# TTeC_Sheet1.net
KiCad netlist of a schematic drawn in Altium Designer
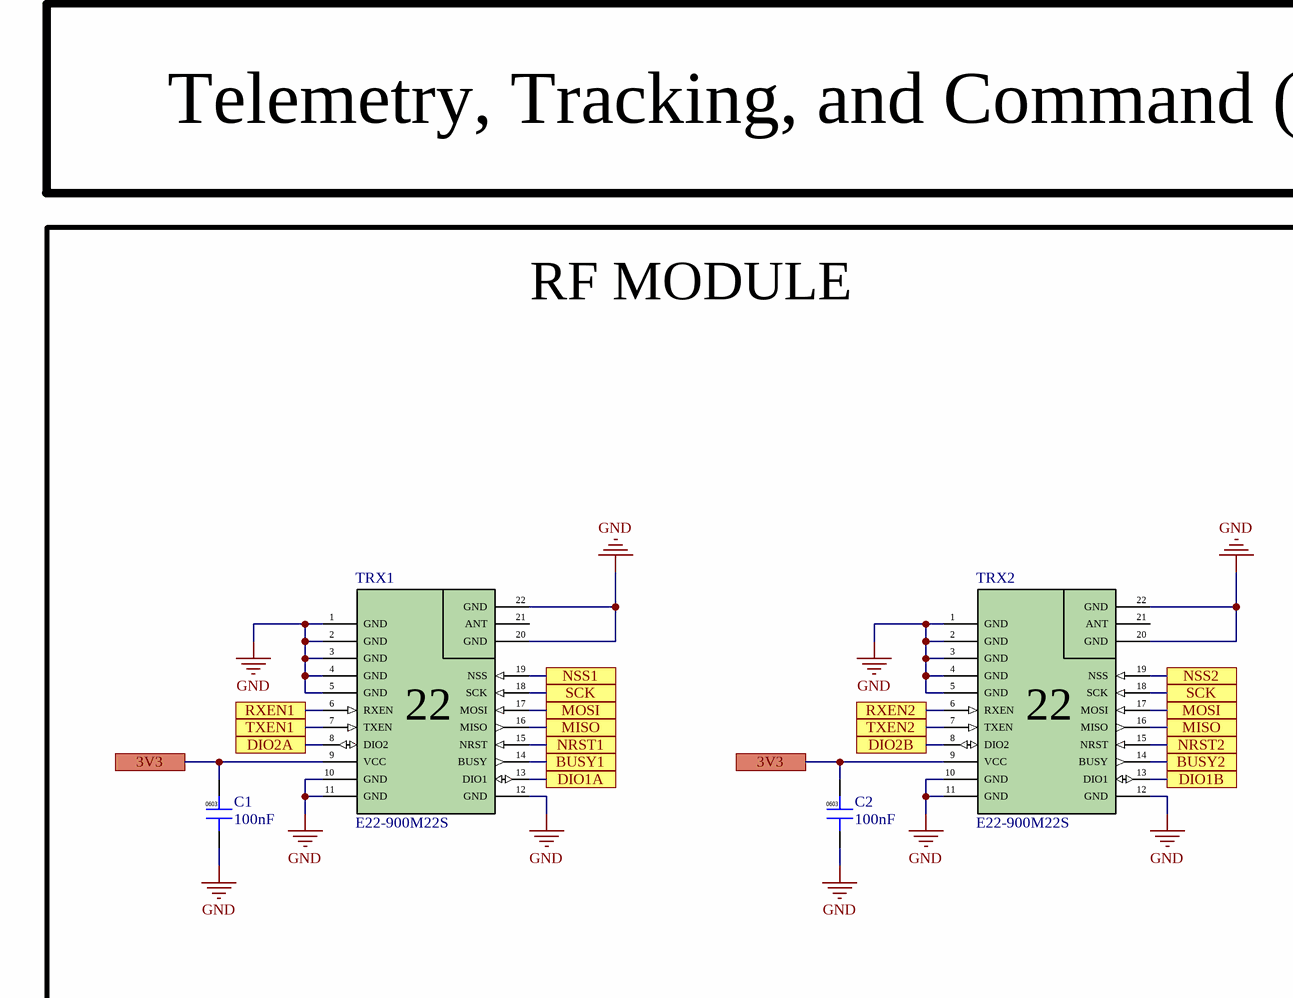
[diagram p0: TTeC_Sheet1.SchDoc, left]
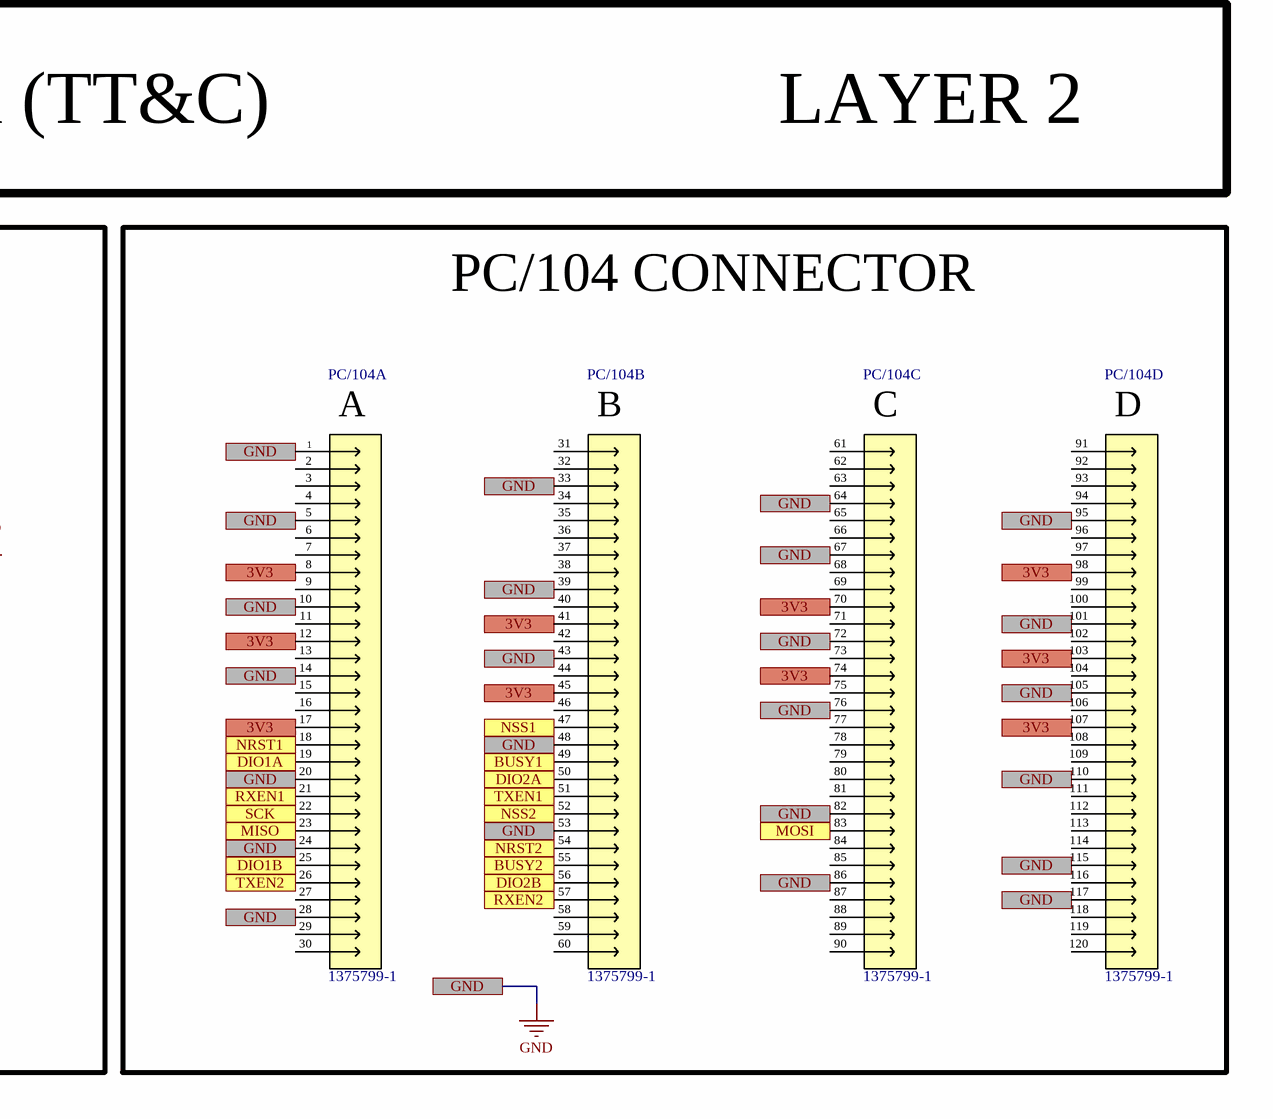
[diagram p1: TTeC_Sheet1.SchDoc, right]

(export (version "E")
  (design (tool "Eeschema 10.0.6"))
  (components
    (comp (ref "C1")
      (value "100nF")
      (footprint "CAP0603_060")
      (description "Capacitor SDM 0603")
      (libsource (lib "componentes_Henrique_V1") (part "CAP0603"))
    )
    (comp (ref "C2")
      (value "100nF")
      (footprint "CAP0603_060")
      (description "Capacitor SDM 0603")
      (libsource (lib "componentes_Henrique_V1") (part "CAP0603"))
    )
    (comp (ref "PC/104")
      (value "1375799-1")
      (footprint "1375799-1")
      (libsource (lib "componentes_Henrique_V1") (part "1375799-1"))
    )
    (comp (ref "TRX1")
      (value "E22-900M22S")
      (footprint "E22-900M22S")
      (libsource (lib "componentes_Henrique_V1") (part "E22-900M22S"))
    )
    (comp (ref "TRX2")
      (value "E22-900M22S")
      (footprint "E22-900M22S")
      (libsource (lib "componentes_Henrique_V1") (part "E22-900M22S"))
    )
  )
  (nets
    (net (code "1") (name "/3V3") (class "Default")
      (node (ref "C1") (pin "1") (pinfunction "1_1") (pintype "passive"))
      (node (ref "C2") (pin "1") (pinfunction "1_1") (pintype "passive"))
      (node (ref "PC/104") (pin "103") (pinfunction "103_103") (pintype "passive"))
      (node (ref "PC/104") (pin "107") (pinfunction "107_107") (pintype "passive"))
      (node (ref "PC/104") (pin "12") (pinfunction "12_12") (pintype "passive"))
      (node (ref "PC/104") (pin "17") (pinfunction "17_17") (pintype "passive"))
      (node (ref "PC/104") (pin "41") (pinfunction "41_41") (pintype "passive"))
      (node (ref "PC/104") (pin "45") (pinfunction "45_45") (pintype "passive"))
      (node (ref "PC/104") (pin "70") (pinfunction "70_70") (pintype "passive"))
      (node (ref "PC/104") (pin "74") (pinfunction "74_74") (pintype "passive"))
      (node (ref "PC/104") (pin "8") (pinfunction "8_8") (pintype "passive"))
      (node (ref "PC/104") (pin "98") (pinfunction "98_98") (pintype "passive"))
      (node (ref "TRX1") (pin "9") (pinfunction "VCC_9") (pintype "passive"))
      (node (ref "TRX2") (pin "9") (pinfunction "VCC_9") (pintype "passive"))
    )
    (net (code "2") (name "/BUSY1") (class "Default")
      (node (ref "PC/104") (pin "49") (pinfunction "49_49") (pintype "passive"))
      (node (ref "TRX1") (pin "14") (pinfunction "BUSY_14") (pintype "output"))
    )
    (net (code "3") (name "/BUSY2") (class "Default")
      (node (ref "PC/104") (pin "55") (pinfunction "55_55") (pintype "passive"))
      (node (ref "TRX2") (pin "14") (pinfunction "BUSY_14") (pintype "output"))
    )
    (net (code "4") (name "/DIO1A") (class "Default")
      (node (ref "PC/104") (pin "19") (pinfunction "19_19") (pintype "passive"))
      (node (ref "TRX1") (pin "13") (pinfunction "DIO1_13") (pintype "bidirectional"))
    )
    (net (code "5") (name "/DIO1B") (class "Default")
      (node (ref "PC/104") (pin "25") (pinfunction "25_25") (pintype "passive"))
      (node (ref "TRX2") (pin "13") (pinfunction "DIO1_13") (pintype "bidirectional"))
    )
    (net (code "6") (name "/DIO2A") (class "Default")
      (node (ref "PC/104") (pin "50") (pinfunction "50_50") (pintype "passive"))
      (node (ref "TRX1") (pin "8") (pinfunction "DIO2_8") (pintype "bidirectional"))
    )
    (net (code "7") (name "/DIO2B") (class "Default")
      (node (ref "PC/104") (pin "56") (pinfunction "56_56") (pintype "passive"))
      (node (ref "TRX2") (pin "8") (pinfunction "DIO2_8") (pintype "bidirectional"))
    )
    (net (code "8") (name "/MISO") (class "Default")
      (node (ref "PC/104") (pin "23") (pinfunction "23_23") (pintype "passive"))
      (node (ref "TRX1") (pin "16") (pinfunction "MISO_16") (pintype "output"))
      (node (ref "TRX2") (pin "16") (pinfunction "MISO_16") (pintype "output"))
    )
    (net (code "9") (name "/MOSI") (class "Default")
      (node (ref "PC/104") (pin "83") (pinfunction "83_83") (pintype "passive"))
      (node (ref "TRX1") (pin "17") (pinfunction "MOSI_17") (pintype "input"))
      (node (ref "TRX2") (pin "17") (pinfunction "MOSI_17") (pintype "input"))
    )
    (net (code "10") (name "/NRST1") (class "Default")
      (node (ref "PC/104") (pin "18") (pinfunction "18_18") (pintype "passive"))
      (node (ref "TRX1") (pin "15") (pinfunction "NRST_15") (pintype "input"))
    )
    (net (code "11") (name "/NRST2") (class "Default")
      (node (ref "PC/104") (pin "54") (pinfunction "54_54") (pintype "passive"))
      (node (ref "TRX2") (pin "15") (pinfunction "NRST_15") (pintype "input"))
    )
    (net (code "12") (name "/NSS1") (class "Default")
      (node (ref "PC/104") (pin "47") (pinfunction "47_47") (pintype "passive"))
      (node (ref "TRX1") (pin "19") (pinfunction "NSS_19") (pintype "input"))
    )
    (net (code "13") (name "/NSS2") (class "Default")
      (node (ref "PC/104") (pin "52") (pinfunction "52_52") (pintype "passive"))
      (node (ref "TRX2") (pin "19") (pinfunction "NSS_19") (pintype "input"))
    )
    (net (code "14") (name "/RXEN1") (class "Default")
      (node (ref "PC/104") (pin "21") (pinfunction "21_21") (pintype "passive"))
      (node (ref "TRX1") (pin "6") (pinfunction "RXEN_6") (pintype "input"))
    )
    (net (code "15") (name "/RXEN2") (class "Default")
      (node (ref "PC/104") (pin "57") (pinfunction "57_57") (pintype "passive"))
      (node (ref "TRX2") (pin "6") (pinfunction "RXEN_6") (pintype "input"))
    )
    (net (code "16") (name "/SCK") (class "Default")
      (node (ref "PC/104") (pin "22") (pinfunction "22_22") (pintype "passive"))
      (node (ref "TRX1") (pin "18") (pinfunction "SCK_18") (pintype "input"))
      (node (ref "TRX2") (pin "18") (pinfunction "SCK_18") (pintype "input"))
    )
    (net (code "17") (name "/TXEN1") (class "Default")
      (node (ref "PC/104") (pin "51") (pinfunction "51_51") (pintype "passive"))
      (node (ref "TRX1") (pin "7") (pinfunction "TXEN_7") (pintype "input"))
    )
    (net (code "18") (name "/TXEN2") (class "Default")
      (node (ref "PC/104") (pin "26") (pinfunction "26_26") (pintype "passive"))
      (node (ref "TRX2") (pin "7") (pinfunction "TXEN_7") (pintype "input"))
    )
    (net (code "19") (name "GND") (class "Default")
      (node (ref "C1") (pin "2") (pinfunction "2_2") (pintype "passive"))
      (node (ref "C2") (pin "2") (pinfunction "2_2") (pintype "passive"))
      (node (ref "PC/104") (pin "1") (pinfunction "1_1") (pintype "passive"))
      (node (ref "PC/104") (pin "10") (pinfunction "10_10") (pintype "passive"))
      (node (ref "PC/104") (pin "101") (pinfunction "101_101") (pintype "passive"))
      (node (ref "PC/104") (pin "105") (pinfunction "105_105") (pintype "passive"))
      (node (ref "PC/104") (pin "110") (pinfunction "110_110") (pintype "passive"))
      (node (ref "PC/104") (pin "115") (pinfunction "115_115") (pintype "passive"))
      (node (ref "PC/104") (pin "117") (pinfunction "117_117") (pintype "passive"))
      (node (ref "PC/104") (pin "14") (pinfunction "14_14") (pintype "passive"))
      (node (ref "PC/104") (pin "20") (pinfunction "20_20") (pintype "passive"))
      (node (ref "PC/104") (pin "24") (pinfunction "24_24") (pintype "passive"))
      (node (ref "PC/104") (pin "28") (pinfunction "28_28") (pintype "passive"))
      (node (ref "PC/104") (pin "33") (pinfunction "33_33") (pintype "passive"))
      (node (ref "PC/104") (pin "39") (pinfunction "39_39") (pintype "passive"))
      (node (ref "PC/104") (pin "43") (pinfunction "43_43") (pintype "passive"))
      (node (ref "PC/104") (pin "48") (pinfunction "48_48") (pintype "passive"))
      (node (ref "PC/104") (pin "5") (pinfunction "5_5") (pintype "passive"))
      (node (ref "PC/104") (pin "53") (pinfunction "53_53") (pintype "passive"))
      (node (ref "PC/104") (pin "64") (pinfunction "64_64") (pintype "passive"))
      (node (ref "PC/104") (pin "67") (pinfunction "67_67") (pintype "passive"))
      (node (ref "PC/104") (pin "72") (pinfunction "72_72") (pintype "passive"))
      (node (ref "PC/104") (pin "76") (pinfunction "76_76") (pintype "passive"))
      (node (ref "PC/104") (pin "82") (pinfunction "82_82") (pintype "passive"))
      (node (ref "PC/104") (pin "86") (pinfunction "86_86") (pintype "passive"))
      (node (ref "PC/104") (pin "95") (pinfunction "95_95") (pintype "passive"))
      (node (ref "TRX1") (pin "1") (pinfunction "GND_1") (pintype "passive"))
      (node (ref "TRX1") (pin "10") (pinfunction "GND_10") (pintype "passive"))
      (node (ref "TRX1") (pin "11") (pinfunction "GND_11") (pintype "passive"))
      (node (ref "TRX1") (pin "12") (pinfunction "GND_12") (pintype "passive"))
      (node (ref "TRX1") (pin "2") (pinfunction "GND_2") (pintype "passive"))
      (node (ref "TRX1") (pin "20") (pinfunction "GND_20") (pintype "passive"))
      (node (ref "TRX1") (pin "22") (pinfunction "GND_22") (pintype "passive"))
      (node (ref "TRX1") (pin "3") (pinfunction "GND_3") (pintype "passive"))
      (node (ref "TRX1") (pin "4") (pinfunction "GND_4") (pintype "passive"))
      (node (ref "TRX1") (pin "5") (pinfunction "GND_5") (pintype "passive"))
      (node (ref "TRX2") (pin "1") (pinfunction "GND_1") (pintype "passive"))
      (node (ref "TRX2") (pin "10") (pinfunction "GND_10") (pintype "passive"))
      (node (ref "TRX2") (pin "11") (pinfunction "GND_11") (pintype "passive"))
      (node (ref "TRX2") (pin "12") (pinfunction "GND_12") (pintype "passive"))
      (node (ref "TRX2") (pin "2") (pinfunction "GND_2") (pintype "passive"))
      (node (ref "TRX2") (pin "20") (pinfunction "GND_20") (pintype "passive"))
      (node (ref "TRX2") (pin "22") (pinfunction "GND_22") (pintype "passive"))
      (node (ref "TRX2") (pin "3") (pinfunction "GND_3") (pintype "passive"))
      (node (ref "TRX2") (pin "4") (pinfunction "GND_4") (pintype "passive"))
      (node (ref "TRX2") (pin "5") (pinfunction "GND_5") (pintype "passive"))
    )
    (net (code "20") (name "unconnected-(PC/104-Pad2)") (class "Default")
      (node (ref "PC/104") (pin "2") (pinfunction "2_2") (pintype "passive"))
    )
    (net (code "21") (name "unconnected-(PC/104-Pad3)") (class "Default")
      (node (ref "PC/104") (pin "3") (pinfunction "3_3") (pintype "passive"))
    )
    (net (code "22") (name "unconnected-(PC/104-Pad4)") (class "Default")
      (node (ref "PC/104") (pin "4") (pinfunction "4_4") (pintype "passive"))
    )
    (net (code "23") (name "unconnected-(PC/104-Pad6)") (class "Default")
      (node (ref "PC/104") (pin "6") (pinfunction "6_6") (pintype "passive"))
    )
    (net (code "24") (name "unconnected-(PC/104-Pad7)") (class "Default")
      (node (ref "PC/104") (pin "7") (pinfunction "7_7") (pintype "passive"))
    )
    (net (code "25") (name "unconnected-(PC/104-Pad9)") (class "Default")
      (node (ref "PC/104") (pin "9") (pinfunction "9_9") (pintype "passive"))
    )
    (net (code "26") (name "unconnected-(PC/104-Pad11)") (class "Default")
      (node (ref "PC/104") (pin "11") (pinfunction "11_11") (pintype "passive"))
    )
    (net (code "27") (name "unconnected-(PC/104-Pad13)") (class "Default")
      (node (ref "PC/104") (pin "13") (pinfunction "13_13") (pintype "passive"))
    )
    (net (code "28") (name "unconnected-(PC/104-Pad15)") (class "Default")
      (node (ref "PC/104") (pin "15") (pinfunction "15_15") (pintype "passive"))
    )
    (net (code "29") (name "unconnected-(PC/104-Pad16)") (class "Default")
      (node (ref "PC/104") (pin "16") (pinfunction "16_16") (pintype "passive"))
    )
    (net (code "30") (name "unconnected-(PC/104-Pad27)") (class "Default")
      (node (ref "PC/104") (pin "27") (pinfunction "27_27") (pintype "passive"))
    )
    (net (code "31") (name "unconnected-(PC/104-Pad29)") (class "Default")
      (node (ref "PC/104") (pin "29") (pinfunction "29_29") (pintype "passive"))
    )
    (net (code "32") (name "unconnected-(PC/104-Pad30)") (class "Default")
      (node (ref "PC/104") (pin "30") (pinfunction "30_30") (pintype "passive"))
    )
    (net (code "33") (name "unconnected-(PC/104-Pad31)") (class "Default")
      (node (ref "PC/104") (pin "31") (pinfunction "31_31") (pintype "passive"))
    )
    (net (code "34") (name "unconnected-(PC/104-Pad32)") (class "Default")
      (node (ref "PC/104") (pin "32") (pinfunction "32_32") (pintype "passive"))
    )
    (net (code "35") (name "unconnected-(PC/104-Pad34)") (class "Default")
      (node (ref "PC/104") (pin "34") (pinfunction "34_34") (pintype "passive"))
    )
    (net (code "36") (name "unconnected-(PC/104-Pad35)") (class "Default")
      (node (ref "PC/104") (pin "35") (pinfunction "35_35") (pintype "passive"))
    )
    (net (code "37") (name "unconnected-(PC/104-Pad36)") (class "Default")
      (node (ref "PC/104") (pin "36") (pinfunction "36_36") (pintype "passive"))
    )
    (net (code "38") (name "unconnected-(PC/104-Pad37)") (class "Default")
      (node (ref "PC/104") (pin "37") (pinfunction "37_37") (pintype "passive"))
    )
    (net (code "39") (name "unconnected-(PC/104-Pad38)") (class "Default")
      (node (ref "PC/104") (pin "38") (pinfunction "38_38") (pintype "passive"))
    )
    (net (code "40") (name "unconnected-(PC/104-Pad40)") (class "Default")
      (node (ref "PC/104") (pin "40") (pinfunction "40_40") (pintype "passive"))
    )
    (net (code "41") (name "unconnected-(PC/104-Pad42)") (class "Default")
      (node (ref "PC/104") (pin "42") (pinfunction "42_42") (pintype "passive"))
    )
    (net (code "42") (name "unconnected-(PC/104-Pad44)") (class "Default")
      (node (ref "PC/104") (pin "44") (pinfunction "44_44") (pintype "passive"))
    )
    (net (code "43") (name "unconnected-(PC/104-Pad46)") (class "Default")
      (node (ref "PC/104") (pin "46") (pinfunction "46_46") (pintype "passive"))
    )
    (net (code "44") (name "unconnected-(PC/104-Pad58)") (class "Default")
      (node (ref "PC/104") (pin "58") (pinfunction "58_58") (pintype "passive"))
    )
    (net (code "45") (name "unconnected-(PC/104-Pad59)") (class "Default")
      (node (ref "PC/104") (pin "59") (pinfunction "59_59") (pintype "passive"))
    )
    (net (code "46") (name "unconnected-(PC/104-Pad60)") (class "Default")
      (node (ref "PC/104") (pin "60") (pinfunction "60_60") (pintype "passive"))
    )
    (net (code "47") (name "unconnected-(PC/104-Pad61)") (class "Default")
      (node (ref "PC/104") (pin "61") (pinfunction "61_61") (pintype "passive"))
    )
    (net (code "48") (name "unconnected-(PC/104-Pad62)") (class "Default")
      (node (ref "PC/104") (pin "62") (pinfunction "62_62") (pintype "passive"))
    )
    (net (code "49") (name "unconnected-(PC/104-Pad63)") (class "Default")
      (node (ref "PC/104") (pin "63") (pinfunction "63_63") (pintype "passive"))
    )
    (net (code "50") (name "unconnected-(PC/104-Pad65)") (class "Default")
      (node (ref "PC/104") (pin "65") (pinfunction "65_65") (pintype "passive"))
    )
    (net (code "51") (name "unconnected-(PC/104-Pad66)") (class "Default")
      (node (ref "PC/104") (pin "66") (pinfunction "66_66") (pintype "passive"))
    )
    (net (code "52") (name "unconnected-(PC/104-Pad68)") (class "Default")
      (node (ref "PC/104") (pin "68") (pinfunction "68_68") (pintype "passive"))
    )
    (net (code "53") (name "unconnected-(PC/104-Pad69)") (class "Default")
      (node (ref "PC/104") (pin "69") (pinfunction "69_69") (pintype "passive"))
    )
    (net (code "54") (name "unconnected-(PC/104-Pad71)") (class "Default")
      (node (ref "PC/104") (pin "71") (pinfunction "71_71") (pintype "passive"))
    )
    (net (code "55") (name "unconnected-(PC/104-Pad73)") (class "Default")
      (node (ref "PC/104") (pin "73") (pinfunction "73_73") (pintype "passive"))
    )
    (net (code "56") (name "unconnected-(PC/104-Pad75)") (class "Default")
      (node (ref "PC/104") (pin "75") (pinfunction "75_75") (pintype "passive"))
    )
    (net (code "57") (name "unconnected-(PC/104-Pad77)") (class "Default")
      (node (ref "PC/104") (pin "77") (pinfunction "77_77") (pintype "passive"))
    )
    (net (code "58") (name "unconnected-(PC/104-Pad78)") (class "Default")
      (node (ref "PC/104") (pin "78") (pinfunction "78_78") (pintype "passive"))
    )
    (net (code "59") (name "unconnected-(PC/104-Pad79)") (class "Default")
      (node (ref "PC/104") (pin "79") (pinfunction "79_79") (pintype "passive"))
    )
    (net (code "60") (name "unconnected-(PC/104-Pad80)") (class "Default")
      (node (ref "PC/104") (pin "80") (pinfunction "80_80") (pintype "passive"))
    )
    (net (code "61") (name "unconnected-(PC/104-Pad81)") (class "Default")
      (node (ref "PC/104") (pin "81") (pinfunction "81_81") (pintype "passive"))
    )
    (net (code "62") (name "unconnected-(PC/104-Pad84)") (class "Default")
      (node (ref "PC/104") (pin "84") (pinfunction "84_84") (pintype "passive"))
    )
    (net (code "63") (name "unconnected-(PC/104-Pad85)") (class "Default")
      (node (ref "PC/104") (pin "85") (pinfunction "85_85") (pintype "passive"))
    )
    (net (code "64") (name "unconnected-(PC/104-Pad87)") (class "Default")
      (node (ref "PC/104") (pin "87") (pinfunction "87_87") (pintype "passive"))
    )
    (net (code "65") (name "unconnected-(PC/104-Pad88)") (class "Default")
      (node (ref "PC/104") (pin "88") (pinfunction "88_88") (pintype "passive"))
    )
    (net (code "66") (name "unconnected-(PC/104-Pad89)") (class "Default")
      (node (ref "PC/104") (pin "89") (pinfunction "89_89") (pintype "passive"))
    )
    (net (code "67") (name "unconnected-(PC/104-Pad90)") (class "Default")
      (node (ref "PC/104") (pin "90") (pinfunction "90_90") (pintype "passive"))
    )
    (net (code "68") (name "unconnected-(PC/104-Pad91)") (class "Default")
      (node (ref "PC/104") (pin "91") (pinfunction "91_91") (pintype "passive"))
    )
    (net (code "69") (name "unconnected-(PC/104-Pad92)") (class "Default")
      (node (ref "PC/104") (pin "92") (pinfunction "92_92") (pintype "passive"))
    )
    (net (code "70") (name "unconnected-(PC/104-Pad93)") (class "Default")
      (node (ref "PC/104") (pin "93") (pinfunction "93_93") (pintype "passive"))
    )
    (net (code "71") (name "unconnected-(PC/104-Pad94)") (class "Default")
      (node (ref "PC/104") (pin "94") (pinfunction "94_94") (pintype "passive"))
    )
    (net (code "72") (name "unconnected-(PC/104-Pad96)") (class "Default")
      (node (ref "PC/104") (pin "96") (pinfunction "96_96") (pintype "passive"))
    )
    (net (code "73") (name "unconnected-(PC/104-Pad97)") (class "Default")
      (node (ref "PC/104") (pin "97") (pinfunction "97_97") (pintype "passive"))
    )
    (net (code "74") (name "unconnected-(PC/104-Pad99)") (class "Default")
      (node (ref "PC/104") (pin "99") (pinfunction "99_99") (pintype "passive"))
    )
    (net (code "75") (name "unconnected-(PC/104-Pad100)") (class "Default")
      (node (ref "PC/104") (pin "100") (pinfunction "100_100") (pintype "passive"))
    )
    (net (code "76") (name "unconnected-(PC/104-Pad102)") (class "Default")
      (node (ref "PC/104") (pin "102") (pinfunction "102_102") (pintype "passive"))
    )
    (net (code "77") (name "unconnected-(PC/104-Pad104)") (class "Default")
      (node (ref "PC/104") (pin "104") (pinfunction "104_104") (pintype "passive"))
    )
    (net (code "78") (name "unconnected-(PC/104-Pad106)") (class "Default")
      (node (ref "PC/104") (pin "106") (pinfunction "106_106") (pintype "passive"))
    )
    (net (code "79") (name "unconnected-(PC/104-Pad108)") (class "Default")
      (node (ref "PC/104") (pin "108") (pinfunction "108_108") (pintype "passive"))
    )
    (net (code "80") (name "unconnected-(PC/104-Pad109)") (class "Default")
      (node (ref "PC/104") (pin "109") (pinfunction "109_109") (pintype "passive"))
    )
    (net (code "81") (name "unconnected-(PC/104-Pad111)") (class "Default")
      (node (ref "PC/104") (pin "111") (pinfunction "111_111") (pintype "passive"))
    )
    (net (code "82") (name "unconnected-(PC/104-Pad112)") (class "Default")
      (node (ref "PC/104") (pin "112") (pinfunction "112_112") (pintype "passive"))
    )
    (net (code "83") (name "unconnected-(PC/104-Pad113)") (class "Default")
      (node (ref "PC/104") (pin "113") (pinfunction "113_113") (pintype "passive"))
    )
    (net (code "84") (name "unconnected-(PC/104-Pad114)") (class "Default")
      (node (ref "PC/104") (pin "114") (pinfunction "114_114") (pintype "passive"))
    )
    (net (code "85") (name "unconnected-(PC/104-Pad116)") (class "Default")
      (node (ref "PC/104") (pin "116") (pinfunction "116_116") (pintype "passive"))
    )
    (net (code "86") (name "unconnected-(PC/104-Pad118)") (class "Default")
      (node (ref "PC/104") (pin "118") (pinfunction "118_118") (pintype "passive"))
    )
    (net (code "87") (name "unconnected-(PC/104-Pad119)") (class "Default")
      (node (ref "PC/104") (pin "119") (pinfunction "119_119") (pintype "passive"))
    )
    (net (code "88") (name "unconnected-(PC/104-Pad120)") (class "Default")
      (node (ref "PC/104") (pin "120") (pinfunction "120_120") (pintype "passive"))
    )
    (net (code "89") (name "unconnected-(TRX1-ANT-Pad21)") (class "Default")
      (node (ref "TRX1") (pin "21") (pinfunction "ANT_21") (pintype "passive"))
    )
    (net (code "90") (name "unconnected-(TRX2-ANT-Pad21)") (class "Default")
      (node (ref "TRX2") (pin "21") (pinfunction "ANT_21") (pintype "passive"))
    )
  )
)
